# Hall-Effect-Switch.net
KiCad netlist of a schematic drawn in Altium Designer
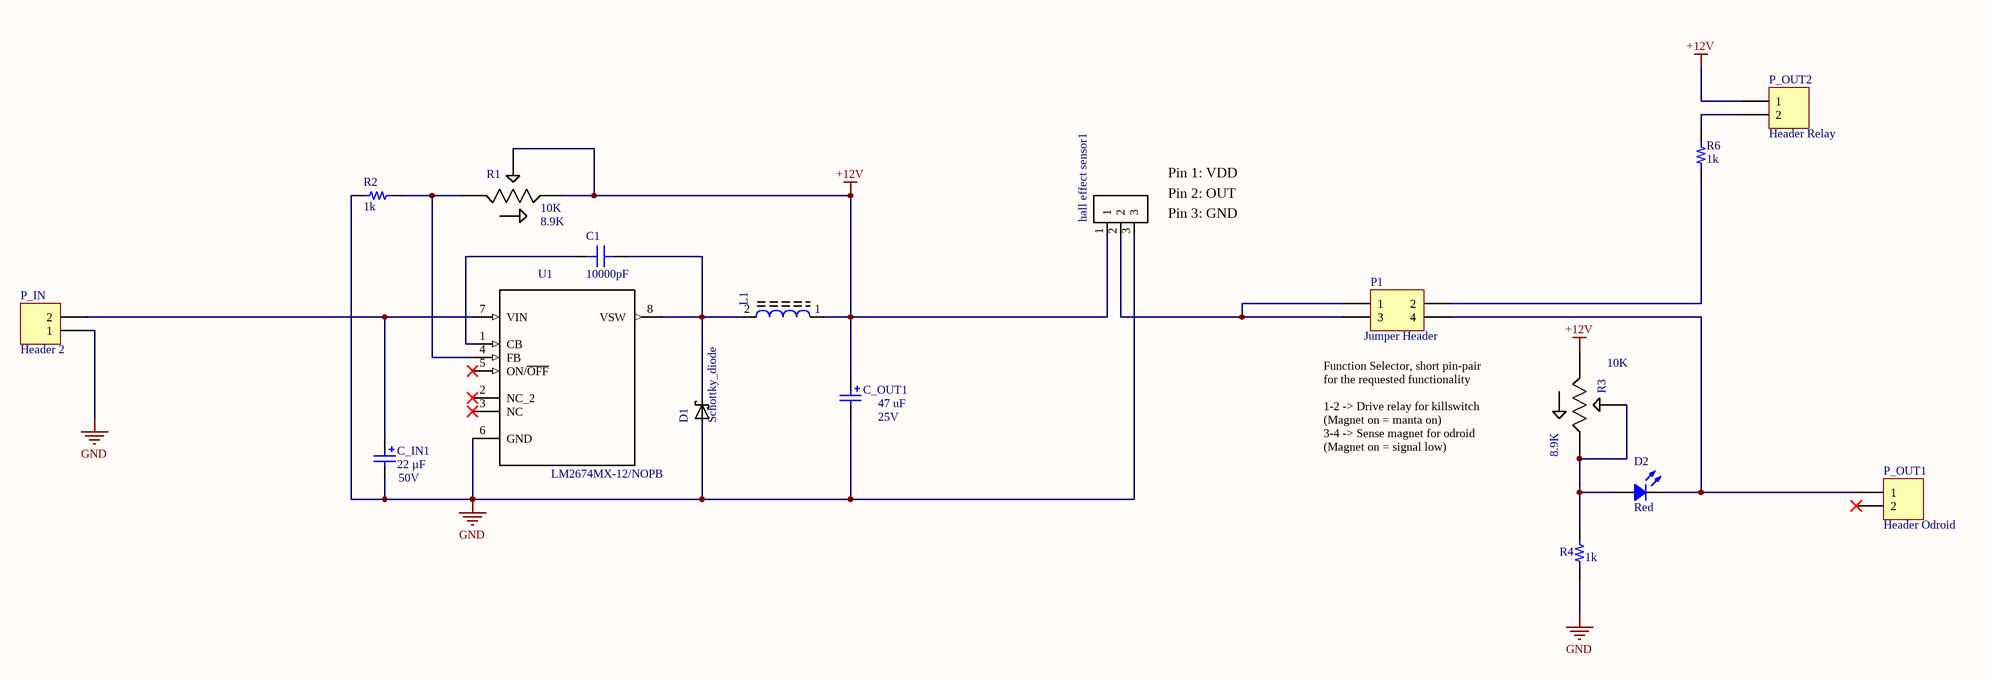
[diagram p0: Hall-Effect-Switch.SchDoc]

(export (version "E")
  (design (tool "Eeschema 10.0.6"))
  (components
    (comp (ref "C1")
      (value "10000pF")
      (footprint "CAP 0805/2012")
      (description "CAP CER 10000PF 50V C0G 0805")
      (fields
        (field (name "PART NUMBER") "C2012C0G1H103J060AA")
        (field (name "MANUFACTURER") "TDK Corporation")
      )
      (libsource (lib "Celestial Library Database") (part "Capacitor"))
    )
    (comp (ref "C_IN1")
      (value "22 µF")
      (footprint "CAPMP7361X375")
      (fields
        (field (name "PART NUMBER") "CAPMP7361X375")
        (field (name "VOLTAGE RATING") "50V")
        (field (name "TOLERANCE") "± 10%")
      )
      (libsource (lib "Vortex-component-database") (part "Capacitor_polarized"))
    )
    (comp (ref "C_OUT1")
      (value "47 uF")
      (footprint "CAPCP7343X430N")
      (fields
        (field (name "PART NUMBER") "CAPCP7343X430N")
        (field (name "VOLTAGE RATING") "25V")
        (field (name "TOLERANCE") "± 10%")
      )
      (libsource (lib "Vortex-component-database") (part "Capacitor_polarized"))
    )
    (comp (ref "D1")
      (value "Schottky_diode")
      (footprint "DIOM7959X250N")
      (description "General-purpose Schottky diodes")
      (fields (field (name "PART NUMBER") "DIOM7959X250N"))
      (libsource (lib "Vortex-component-database") (part "Schottky_diode"))
    )
    (comp (ref "D2")
      (value "Red")
      (footprint "LED 0603/1608 RED")
      (description "LED RED CLEAR 0603 SMD")
      (fields (field (name "PART NUMBER") "LTST-C191KRKT") (field (name "MANUFACTURER") "Lite-On Inc."))
      (libsource (lib "Celestial Library Database") (part "LED"))
    )
    (comp (ref "hall effect sensor1")
      (value "~")
      (footprint "US5881LSE-AAA-000-RE")
      (description "Digital Switch Unipolar Switch Open Drain Hall Effect SOT-23")
      (fields (field (name "PART NUMBER") "US5881LSE-AAA-000-RE"))
      (libsource (lib "Vortex-component-database") (part "US5881LSE-AAA-000-RE"))
    )
    (comp (ref "L1")
      (value "SRR1260-680M")
      (footprint "SRR1260-680M:SRR1260-680M")
      (description "Ind Power Shielded Wirewound 68uH 20% 100KHz 22Q-Factor Ferrite 2.1A T/R")
      (fields (field (name "MF") "Bourns"))
      (libsource (lib "Vortex-component-database") (part "SRR1260-680M"))
    )
    (comp (ref "P1")
      (value "Jumper Header")
      (footprint "HDR2X2")
      (description "Header, 2-Pin, Dual row")
      (fields (field (name "PUBLISHER") "Altium Limited"))
      (libsource (lib "Miscellaneous Connectors") (part "Header 2X2"))
    )
    (comp (ref "P_IN")
      (value "Header 2")
      (footprint "HDR1X2")
      (description "Header, 2-Pin")
      (fields (field (name "PUBLISHER") "Altium Limited"))
      (libsource (lib "") (part "Header 2_1"))
    )
    (comp (ref "P_OUT1")
      (value "Header Odroid")
      (footprint "HDR1X2")
      (description "Header, 2-Pin")
      (fields (field (name "PUBLISHER") "Altium Limited"))
      (libsource (lib "Miscellaneous Connectors") (part "Header 2"))
    )
    (comp (ref "P_OUT2")
      (value "Header Relay")
      (footprint "HDR1X2")
      (description "Header, 2-Pin")
      (fields (field (name "PUBLISHER") "Altium Limited"))
      (libsource (lib "Miscellaneous Connectors") (part "Header 2"))
    )
    (comp (ref "R1")
      (value "8.9K")
      (footprint "*35WR")
      (description "Res Trimmer 10K Ohm 25% 0.1W_1/10W_ 1_Elec_/1_Mech_Turn _3 X 3.8mm_ Foot Print SMD Embossed T/R")
      (fields
        (field (name "MP") "TC33X-2-103E")
        (field (name "MF") "Bourns")
        (field (name "ALTIUM_VALUE") "10K")
      )
      (libsource (lib "Vortex-component-database") (part "TC33X-2-103E"))
    )
    (comp (ref "R2")
      (value "1k")
      (footprint "RES 0805/2012")
      (description "RES SMD 1K OHM 1% 1/8W 0805")
      (fields
        (field (name "PART NUMBER") "ERJ-6ENF1001V")
        (field (name "MANUFACTURER") "Panasonic Electronic Components")
      )
      (libsource (lib "Celestial Library Database") (part "Resistor"))
    )
    (comp (ref "R3")
      (value "8.9K")
      (footprint "*35WR")
      (description "Res Trimmer 10K Ohm 25% 0.1W_1/10W_ 1_Elec_/1_Mech_Turn _3 X 3.8mm_ Foot Print SMD Embossed T/R")
      (fields
        (field (name "MP") "TC33X-2-103E")
        (field (name "MF") "Bourns")
        (field (name "ALTIUM_VALUE") "10K")
      )
      (libsource (lib "Vortex-component-database") (part "TC33X-2-103E"))
    )
    (comp (ref "R4")
      (value "1k")
      (footprint "RES 0805/2012")
      (description "RES SMD 1K OHM 1% 1/8W 0805")
      (fields
        (field (name "PART NUMBER") "ERJ-6ENF1001V")
        (field (name "MANUFACTURER") "Panasonic Electronic Components")
      )
      (libsource (lib "Celestial Library Database") (part "Resistor"))
    )
    (comp (ref "R6")
      (value "1k")
      (footprint "RES 0805/2012")
      (description "RES SMD 1K OHM 1% 1/8W 0805")
      (fields
        (field (name "PART NUMBER") "ERJ-6ENF1001V")
        (field (name "MANUFACTURER") "Panasonic Electronic Components")
      )
      (libsource (lib "Celestial Library Database") (part "Resistor"))
    )
    (comp (ref "U1")
      (value "LM2674MX-12/NOPB")
      (footprint "LM2674MX-12_NOPB")
      (description "SIMPLE SWITCHERÂ® 40V, 500mA Low Component Count Step-Down Regulator 8-SOIC -40 to 125")
      (fields (field (name "MF") "Texas Instruments") (field (name "PART NUMBER") "LM2674MX-12_NOPB"))
      (libsource (lib "Vortex-component-database") (part "LM2674MX-12/NOPB"))
    )
  )
  (nets
    (net (code "1") (name "+12V") (class "Default")
      (node (ref "C_OUT1") (pin "1") (pinfunction "1_1") (pintype "passive"))
      (node (ref "L1") (pin "1") (pinfunction "1_1") (pintype "passive"))
      (node (ref "P_OUT2") (pin "1") (pinfunction "1_1") (pintype "passive"))
      (node (ref "R1") (pin "2") (pinfunction "2_2") (pintype "passive"))
      (node (ref "R1") (pin "3") (pinfunction "3_3") (pintype "passive"))
      (node (ref "R3") (pin "1") (pinfunction "1_1") (pintype "passive"))
      (node (ref "hall effect sensor1") (pin "1") (pinfunction "1_1") (pintype "passive"))
    )
    (net (code "2") (name "GND") (class "Default")
      (node (ref "C_IN1") (pin "2") (pinfunction "2_2") (pintype "passive"))
      (node (ref "C_OUT1") (pin "2") (pinfunction "2_2") (pintype "passive"))
      (node (ref "D1") (pin "2") (pinfunction "A_2") (pintype "passive"))
      (node (ref "P_IN") (pin "1") (pinfunction "1_1") (pintype "passive"))
      (node (ref "R2") (pin "1") (pinfunction "1_1") (pintype "passive"))
      (node (ref "R4") (pin "1") (pinfunction "1_1") (pintype "passive"))
      (node (ref "U1") (pin "6") (pinfunction "GND_6") (pintype "passive"))
      (node (ref "hall effect sensor1") (pin "3") (pinfunction "3_3") (pintype "passive"))
    )
    (net (code "3") (name "Net-(D1-C)") (class "Default")
      (node (ref "C1") (pin "2") (pinfunction "2_2") (pintype "passive"))
      (node (ref "D1") (pin "1") (pinfunction "C_1") (pintype "passive"))
      (node (ref "L1") (pin "2") (pinfunction "2_2") (pintype "passive"))
      (node (ref "U1") (pin "8") (pinfunction "VSW_8") (pintype "output"))
    )
    (net (code "4") (name "Net-(D2-Pad1)") (class "Default")
      (node (ref "D2") (pin "1") (pinfunction "1_1") (pintype "passive"))
      (node (ref "R3") (pin "2") (pinfunction "2_2") (pintype "passive"))
      (node (ref "R3") (pin "3") (pinfunction "3_3") (pintype "passive"))
      (node (ref "R4") (pin "2") (pinfunction "2_2") (pintype "passive"))
    )
    (net (code "5") (name "Net-(D2-Pad2)") (class "Default")
      (node (ref "D2") (pin "2") (pinfunction "2_2") (pintype "passive"))
      (node (ref "P1") (pin "4") (pinfunction "4_4") (pintype "passive"))
      (node (ref "P_OUT1") (pin "1") (pinfunction "1_1") (pintype "passive"))
    )
    (net (code "6") (name "Net-(P1-Pad1)") (class "Default")
      (node (ref "P1") (pin "1") (pinfunction "1_1") (pintype "passive"))
      (node (ref "P1") (pin "3") (pinfunction "3_3") (pintype "passive"))
      (node (ref "hall effect sensor1") (pin "2") (pinfunction "2_2") (pintype "passive"))
    )
    (net (code "7") (name "Net-(P1-Pad2)") (class "Default")
      (node (ref "P1") (pin "2") (pinfunction "2_2") (pintype "passive"))
      (node (ref "R6") (pin "1") (pinfunction "1_1") (pintype "passive"))
    )
    (net (code "8") (name "Net-(P_OUT2-Pad2)") (class "Default")
      (node (ref "P_OUT2") (pin "2") (pinfunction "2_2") (pintype "passive"))
      (node (ref "R6") (pin "2") (pinfunction "2_2") (pintype "passive"))
    )
    (net (code "9") (name "Net-(U1-CB)") (class "Default")
      (node (ref "C1") (pin "1") (pinfunction "1_1") (pintype "passive"))
      (node (ref "U1") (pin "1") (pinfunction "CB_1") (pintype "input"))
    )
    (net (code "10") (name "Net-(U1-FB)") (class "Default")
      (node (ref "R1") (pin "1") (pinfunction "1_1") (pintype "passive"))
      (node (ref "R2") (pin "2") (pinfunction "2_2") (pintype "passive"))
      (node (ref "U1") (pin "4") (pinfunction "FB_4") (pintype "input"))
    )
    (net (code "11") (name "Net-(U1-VIN)") (class "Default")
      (node (ref "C_IN1") (pin "1") (pinfunction "1_1") (pintype "passive"))
      (node (ref "P_IN") (pin "2") (pinfunction "2_2") (pintype "passive"))
      (node (ref "U1") (pin "7") (pinfunction "VIN_7") (pintype "input"))
    )
    (net (code "12") (name "unconnected-(P_OUT1-Pad2)") (class "Default")
      (node (ref "P_OUT1") (pin "2") (pinfunction "2_2") (pintype "passive+no_connect"))
    )
    (net (code "13") (name "unconnected-(U1-NC-Pad3)") (class "Default")
      (node (ref "U1") (pin "3") (pinfunction "NC_3") (pintype "passive+no_connect"))
    )
    (net (code "14") (name "unconnected-(U1-NC_2-Pad2)") (class "Default")
      (node (ref "U1") (pin "2") (pinfunction "NC_2_2") (pintype "passive+no_connect"))
    )
    (net (code "15") (name "unconnected-(U1-ON{slash}~{OFF}-Pad5)") (class "Default")
      (node (ref "U1") (pin "5") (pinfunction "ON/~{OFF}_5") (pintype "input+no_connect"))
    )
  )
)
